# Sheet_1_2026-05-01.net
KiCad netlist of a schematic drawn in Altium Designer
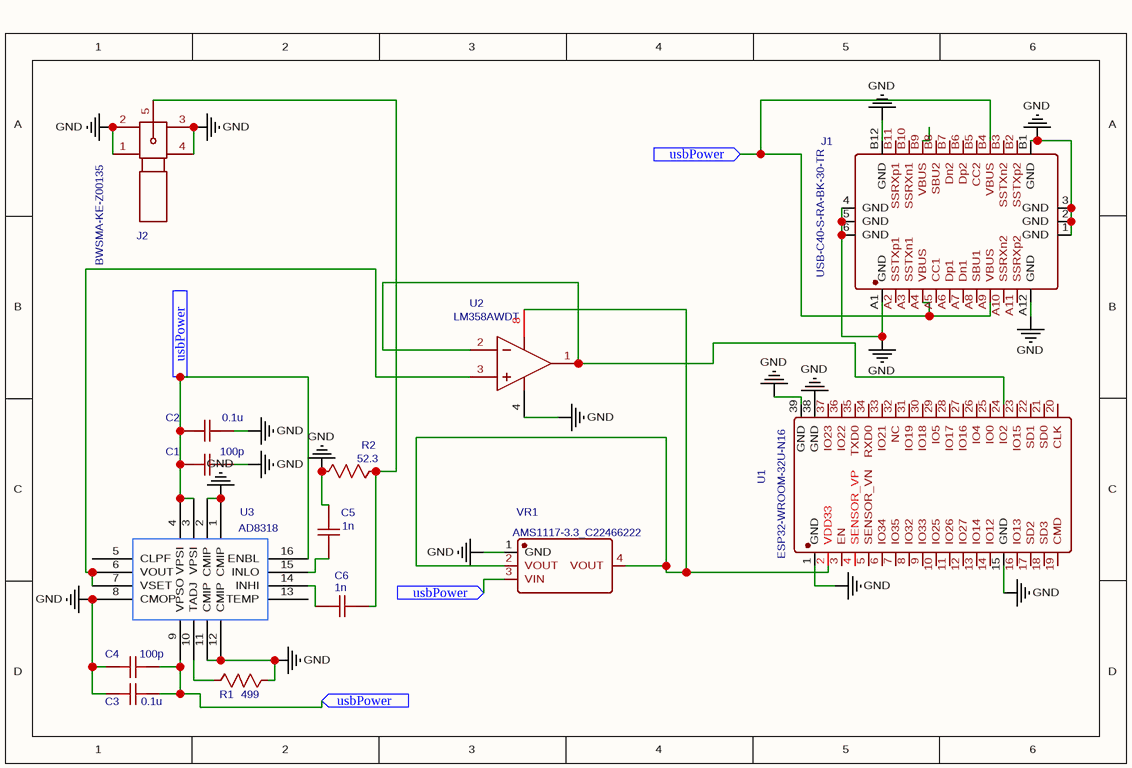
[diagram p0: Sheet_1_2026-05-01.schdoc]

(export (version "E")
  (design (tool "Eeschema 10.0.6"))
  (components
    (comp (ref "C1")
      (value "100p")
      (fields (field (name "CONTRIBUTOR") "LCEDA_Lib"))
      (libsource (lib "altium-import") (part "root_2_100p_"))
    )
    (comp (ref "C2")
      (value "0.1u")
      (fields (field (name "CONTRIBUTOR") "LCEDA_Lib"))
      (libsource (lib "altium-import") (part "root_2_0.1u_"))
    )
    (comp (ref "C3")
      (value "0.1u")
      (fields (field (name "CONTRIBUTOR") "LCEDA_Lib"))
      (libsource (lib "altium-import") (part "root_2_0.1u_"))
    )
    (comp (ref "C4")
      (value "100p")
      (fields (field (name "CONTRIBUTOR") "LCEDA_Lib"))
      (libsource (lib "altium-import") (part "root_2_100p_"))
    )
    (comp (ref "C5")
      (value "1n")
      (fields (field (name "CONTRIBUTOR") "LCEDA_Lib"))
      (libsource (lib "altium-import") (part "root_3_1n_"))
    )
    (comp (ref "C6")
      (value "1n")
      (fields (field (name "CONTRIBUTOR") "LCEDA_Lib"))
      (libsource (lib "altium-import") (part "root_2_1n_"))
    )
    (comp (ref "J1")
      (value "USB-C40-S-RA-BK-30-TR")
      (fields (field (name "MANUFACTURER") "ADAM TECH") (field (name "CONTRIBUTOR") "lcsc"))
      (libsource (lib "altium-import") (part "root_1_USB-C40-S-RA-BK-30-TR_"))
    )
    (comp (ref "J2")
      (value "BWSMA-KE-Z00135")
      (fields
        (field (name "MANUFACTURER") "LX(连欣科技)")
        (field (name "MANUFACTURER PART") "SMA-KWE/KE-135")
        (field (name "CONTRIBUTOR") "lcsc")
      )
      (libsource (lib "altium-import") (part "root_1_BWSMA-KE-Z00135_"))
    )
    (comp (ref "R1")
      (value "499")
      (fields (field (name "CONTRIBUTOR") "LCEDA_Lib"))
      (libsource (lib "altium-import") (part "root_0_499_"))
    )
    (comp (ref "R2")
      (value "52.3")
      (fields (field (name "CONTRIBUTOR") "LCEDA_Lib"))
      (libsource (lib "altium-import") (part "root_2_52.3_"))
    )
    (comp (ref "U1")
      (value "ESP32-WROOM-32U-N16")
      (fields (field (name "MANUFACTURER PART") "ESP32-WROOM-32U(16MB)") (field (name "CONTRIBUTOR") "lcsc"))
      (libsource (lib "altium-import") (part "root_1_ESP32-WROOM-32U-N16_"))
    )
    (comp (ref "U2")
      (value "LM358AWDT")
      (fields (field (name "SUBPART_NO") "1") (field (name "MANUFACTURER") "ST(意法半导体)"))
      (libsource (lib "altium-import") (part "root_0_LM358AWDT_"))
    )
    (comp (ref "U3")
      (value "AD8318")
      (fields (field (name "MANUFACTURER") "Analog Devices") (field (name "CONTRIBUTOR") "kpokigo"))
      (libsource (lib "altium-import") (part "root_3_AD8318_"))
    )
    (comp (ref "VR1")
      (value "AMS1117-3.3_C22466222")
      (fields
        (field (name "MANUFACTURER") "TDSEMIC(拓电半导体)")
        (field (name "MANUFACTURER PART") "AMS1117-3.3")
        (field (name "CONTRIBUTOR") "lcsc")
      )
      (libsource (lib "altium-import") (part "root_0_AMS1117-3.3_C22466222_"))
    )
  )
  (nets
    (net (code "1") (name "/usbPower") (class "Default")
      (node (ref "C1") (pin "2") (pinfunction "2_2") (pintype "passive"))
      (node (ref "C2") (pin "2") (pinfunction "2_2") (pintype "passive"))
      (node (ref "C3") (pin "1") (pinfunction "1_1") (pintype "passive"))
      (node (ref "C4") (pin "1") (pinfunction "1_1") (pintype "passive"))
      (node (ref "J1") (pin "A4") (pinfunction "VBUS_A4") (pintype "passive"))
      (node (ref "J1") (pin "A9") (pinfunction "VBUS_A9") (pintype "passive"))
      (node (ref "J1") (pin "B4") (pinfunction "VBUS_B4") (pintype "passive"))
      (node (ref "U3") (pin "16") (pinfunction "ENBL_16") (pintype "passive"))
      (node (ref "U3") (pin "3") (pinfunction "VPSI_3") (pintype "passive"))
      (node (ref "U3") (pin "4") (pinfunction "VPSI_4") (pintype "passive"))
      (node (ref "U3") (pin "9") (pinfunction "VPSO_9") (pintype "passive"))
      (node (ref "VR1") (pin "3") (pinfunction "VIN_3") (pintype "passive"))
    )
    (net (code "2") (name "GND") (class "Default")
      (node (ref "C1") (pin "1") (pinfunction "1_1") (pintype "passive"))
      (node (ref "C2") (pin "1") (pinfunction "1_1") (pintype "passive"))
      (node (ref "C3") (pin "2") (pinfunction "2_2") (pintype "passive"))
      (node (ref "C4") (pin "2") (pinfunction "2_2") (pintype "passive"))
      (node (ref "C5") (pin "1") (pinfunction "1_1") (pintype "passive"))
      (node (ref "J1") (pin "1") (pinfunction "GND_1") (pintype "passive"))
      (node (ref "J1") (pin "2") (pinfunction "GND_2") (pintype "passive"))
      (node (ref "J1") (pin "3") (pinfunction "GND_3") (pintype "passive"))
      (node (ref "J1") (pin "4") (pinfunction "GND_4") (pintype "passive"))
      (node (ref "J1") (pin "5") (pinfunction "GND_5") (pintype "passive"))
      (node (ref "J1") (pin "6") (pinfunction "GND_6") (pintype "passive"))
      (node (ref "J1") (pin "A1") (pinfunction "GND_A1") (pintype "passive"))
      (node (ref "J1") (pin "A12") (pinfunction "GND_A12") (pintype "passive"))
      (node (ref "J1") (pin "B1") (pinfunction "GND_B1") (pintype "passive"))
      (node (ref "J1") (pin "B12") (pinfunction "GND_B12") (pintype "passive"))
      (node (ref "J2") (pin "1") (pinfunction "1_1") (pintype "passive"))
      (node (ref "J2") (pin "2") (pinfunction "2_2") (pintype "passive"))
      (node (ref "J2") (pin "3") (pinfunction "3_3") (pintype "passive"))
      (node (ref "J2") (pin "4") (pinfunction "4_4") (pintype "passive"))
      (node (ref "R1") (pin "2") (pinfunction "2_2") (pintype "passive"))
      (node (ref "R2") (pin "2") (pinfunction "2_2") (pintype "passive"))
      (node (ref "U1") (pin "1") (pinfunction "GND_1") (pintype "passive"))
      (node (ref "U1") (pin "15") (pinfunction "GND_15") (pintype "passive"))
      (node (ref "U1") (pin "38") (pinfunction "GND_38") (pintype "passive"))
      (node (ref "U1") (pin "39") (pinfunction "GND_39") (pintype "passive"))
      (node (ref "U2") (pin "4") (pinfunction "VCC-_4") (pintype "passive"))
      (node (ref "U3") (pin "1") (pinfunction "CMIP_1") (pintype "passive"))
      (node (ref "U3") (pin "11") (pinfunction "CMIP_11") (pintype "passive"))
      (node (ref "U3") (pin "12") (pinfunction "CMIP_12") (pintype "passive"))
      (node (ref "U3") (pin "2") (pinfunction "CMIP_2") (pintype "passive"))
      (node (ref "U3") (pin "8") (pinfunction "CMOP_8") (pintype "passive"))
      (node (ref "VR1") (pin "1") (pinfunction "GND_1") (pintype "passive"))
    )
    (net (code "3") (name "Net-(C6-Pad1)") (class "Default")
      (node (ref "C6") (pin "1") (pinfunction "1_1") (pintype "passive"))
      (node (ref "J2") (pin "5") (pinfunction "5_5") (pintype "passive"))
      (node (ref "R2") (pin "1") (pinfunction "1_1") (pintype "passive"))
    )
    (net (code "4") (name "Net-(U1-IO2)") (class "Default")
      (node (ref "U1") (pin "24") (pinfunction "IO2_24") (pintype "passive"))
      (node (ref "U2") (pin "1") (pinfunction "OUT1_1") (pintype "passive"))
      (node (ref "U2") (pin "2") (pinfunction "IN1-_2") (pintype "passive"))
    )
    (net (code "5") (name "Net-(U1-VDD33)") (class "Default")
      (node (ref "U1") (pin "2") (pinfunction "VDD33_2") (pintype "passive"))
      (node (ref "U2") (pin "8") (pinfunction "VCC+_8") (pintype "passive"))
      (node (ref "VR1") (pin "2") (pinfunction "VOUT_2") (pintype "passive"))
      (node (ref "VR1") (pin "4") (pinfunction "VOUT_4") (pintype "passive"))
    )
    (net (code "6") (name "Net-(U2-IN1+)") (class "Default")
      (node (ref "U2") (pin "3") (pinfunction "IN1+_3") (pintype "passive"))
      (node (ref "U3") (pin "6") (pinfunction "VOUT_6") (pintype "passive"))
      (node (ref "U3") (pin "7") (pinfunction "VSET_7") (pintype "passive"))
    )
    (net (code "7") (name "Net-(U3-INHI)") (class "Default")
      (node (ref "C6") (pin "2") (pinfunction "2_2") (pintype "passive"))
      (node (ref "U3") (pin "14") (pinfunction "INHI_14") (pintype "passive"))
    )
    (net (code "8") (name "Net-(U3-INLO)") (class "Default")
      (node (ref "C5") (pin "2") (pinfunction "2_2") (pintype "passive"))
      (node (ref "U3") (pin "15") (pinfunction "INLO_15") (pintype "passive"))
    )
    (net (code "9") (name "Net-(U3-TADJ)") (class "Default")
      (node (ref "R1") (pin "1") (pinfunction "1_1") (pintype "passive"))
      (node (ref "U3") (pin "10") (pinfunction "TADJ_10") (pintype "passive"))
    )
    (net (code "10") (name "unconnected-(J1-CC1-PadA5)") (class "Default")
      (node (ref "J1") (pin "A5") (pinfunction "CC1_A5") (pintype "passive"))
    )
    (net (code "11") (name "unconnected-(J1-CC2-PadB5)") (class "Default")
      (node (ref "J1") (pin "B5") (pinfunction "CC2_B5") (pintype "passive"))
    )
    (net (code "12") (name "unconnected-(J1-Dn1-PadA7)") (class "Default")
      (node (ref "J1") (pin "A7") (pinfunction "Dn1_A7") (pintype "passive"))
    )
    (net (code "13") (name "unconnected-(J1-Dn2-PadB7)") (class "Default")
      (node (ref "J1") (pin "B7") (pinfunction "Dn2_B7") (pintype "passive"))
    )
    (net (code "14") (name "unconnected-(J1-Dp1-PadA6)") (class "Default")
      (node (ref "J1") (pin "A6") (pinfunction "Dp1_A6") (pintype "passive"))
    )
    (net (code "15") (name "unconnected-(J1-Dp2-PadB6)") (class "Default")
      (node (ref "J1") (pin "B6") (pinfunction "Dp2_B6") (pintype "passive"))
    )
    (net (code "16") (name "unconnected-(J1-SBU1-PadA8)") (class "Default")
      (node (ref "J1") (pin "A8") (pinfunction "SBU1_A8") (pintype "passive"))
    )
    (net (code "17") (name "unconnected-(J1-SBU2-PadB8)") (class "Default")
      (node (ref "J1") (pin "B8") (pinfunction "SBU2_B8") (pintype "passive"))
    )
    (net (code "18") (name "unconnected-(J1-SSRXn1-PadB10)") (class "Default")
      (node (ref "J1") (pin "B10") (pinfunction "SSRXn1_B10") (pintype "passive"))
    )
    (net (code "19") (name "unconnected-(J1-SSRXn2-PadA10)") (class "Default")
      (node (ref "J1") (pin "A10") (pinfunction "SSRXn2_A10") (pintype "passive"))
    )
    (net (code "20") (name "unconnected-(J1-SSRXp1-PadB11)") (class "Default")
      (node (ref "J1") (pin "B11") (pinfunction "SSRXp1_B11") (pintype "passive"))
    )
    (net (code "21") (name "unconnected-(J1-SSRXp2-PadA11)") (class "Default")
      (node (ref "J1") (pin "A11") (pinfunction "SSRXp2_A11") (pintype "passive"))
    )
    (net (code "22") (name "unconnected-(J1-SSTXn1-PadA3)") (class "Default")
      (node (ref "J1") (pin "A3") (pinfunction "SSTXn1_A3") (pintype "passive"))
    )
    (net (code "23") (name "unconnected-(J1-SSTXn2-PadB3)") (class "Default")
      (node (ref "J1") (pin "B3") (pinfunction "SSTXn2_B3") (pintype "passive"))
    )
    (net (code "24") (name "unconnected-(J1-SSTXp1-PadA2)") (class "Default")
      (node (ref "J1") (pin "A2") (pinfunction "SSTXp1_A2") (pintype "passive"))
    )
    (net (code "25") (name "unconnected-(J1-SSTXp2-PadB2)") (class "Default")
      (node (ref "J1") (pin "B2") (pinfunction "SSTXp2_B2") (pintype "passive"))
    )
    (net (code "26") (name "unconnected-(J1-VBUS-PadB9)") (class "Default")
      (node (ref "J1") (pin "B9") (pinfunction "VBUS_B9") (pintype "passive"))
    )
    (net (code "27") (name "unconnected-(U1-CLK-Pad20)") (class "Default")
      (node (ref "U1") (pin "20") (pinfunction "CLK_20") (pintype "passive"))
    )
    (net (code "28") (name "unconnected-(U1-CMD-Pad19)") (class "Default")
      (node (ref "U1") (pin "19") (pinfunction "CMD_19") (pintype "passive"))
    )
    (net (code "29") (name "unconnected-(U1-EN-Pad3)") (class "Default")
      (node (ref "U1") (pin "3") (pinfunction "EN_3") (pintype "passive"))
    )
    (net (code "30") (name "unconnected-(U1-IO0-Pad25)") (class "Default")
      (node (ref "U1") (pin "25") (pinfunction "IO0_25") (pintype "passive"))
    )
    (net (code "31") (name "unconnected-(U1-IO4-Pad26)") (class "Default")
      (node (ref "U1") (pin "26") (pinfunction "IO4_26") (pintype "passive"))
    )
    (net (code "32") (name "unconnected-(U1-IO5-Pad29)") (class "Default")
      (node (ref "U1") (pin "29") (pinfunction "IO5_29") (pintype "passive"))
    )
    (net (code "33") (name "unconnected-(U1-IO12-Pad14)") (class "Default")
      (node (ref "U1") (pin "14") (pinfunction "IO12_14") (pintype "passive"))
    )
    (net (code "34") (name "unconnected-(U1-IO13-Pad16)") (class "Default")
      (node (ref "U1") (pin "16") (pinfunction "IO13_16") (pintype "passive"))
    )
    (net (code "35") (name "unconnected-(U1-IO14-Pad13)") (class "Default")
      (node (ref "U1") (pin "13") (pinfunction "IO14_13") (pintype "passive"))
    )
    (net (code "36") (name "unconnected-(U1-IO15-Pad23)") (class "Default")
      (node (ref "U1") (pin "23") (pinfunction "IO15_23") (pintype "passive"))
    )
    (net (code "37") (name "unconnected-(U1-IO16-Pad27)") (class "Default")
      (node (ref "U1") (pin "27") (pinfunction "IO16_27") (pintype "passive"))
    )
    (net (code "38") (name "unconnected-(U1-IO17-Pad28)") (class "Default")
      (node (ref "U1") (pin "28") (pinfunction "IO17_28") (pintype "passive"))
    )
    (net (code "39") (name "unconnected-(U1-IO18-Pad30)") (class "Default")
      (node (ref "U1") (pin "30") (pinfunction "IO18_30") (pintype "passive"))
    )
    (net (code "40") (name "unconnected-(U1-IO19-Pad31)") (class "Default")
      (node (ref "U1") (pin "31") (pinfunction "IO19_31") (pintype "passive"))
    )
    (net (code "41") (name "unconnected-(U1-IO21-Pad33)") (class "Default")
      (node (ref "U1") (pin "33") (pinfunction "IO21_33") (pintype "passive"))
    )
    (net (code "42") (name "unconnected-(U1-IO22-Pad36)") (class "Default")
      (node (ref "U1") (pin "36") (pinfunction "IO22_36") (pintype "passive"))
    )
    (net (code "43") (name "unconnected-(U1-IO23-Pad37)") (class "Default")
      (node (ref "U1") (pin "37") (pinfunction "IO23_37") (pintype "passive"))
    )
    (net (code "44") (name "unconnected-(U1-IO25-Pad10)") (class "Default")
      (node (ref "U1") (pin "10") (pinfunction "IO25_10") (pintype "passive"))
    )
    (net (code "45") (name "unconnected-(U1-IO26-Pad11)") (class "Default")
      (node (ref "U1") (pin "11") (pinfunction "IO26_11") (pintype "passive"))
    )
    (net (code "46") (name "unconnected-(U1-IO27-Pad12)") (class "Default")
      (node (ref "U1") (pin "12") (pinfunction "IO27_12") (pintype "passive"))
    )
    (net (code "47") (name "unconnected-(U1-IO32-Pad8)") (class "Default")
      (node (ref "U1") (pin "8") (pinfunction "IO32_8") (pintype "passive"))
    )
    (net (code "48") (name "unconnected-(U1-IO33-Pad9)") (class "Default")
      (node (ref "U1") (pin "9") (pinfunction "IO33_9") (pintype "passive"))
    )
    (net (code "49") (name "unconnected-(U1-IO34-Pad6)") (class "Default")
      (node (ref "U1") (pin "6") (pinfunction "IO34_6") (pintype "passive"))
    )
    (net (code "50") (name "unconnected-(U1-IO35-Pad7)") (class "Default")
      (node (ref "U1") (pin "7") (pinfunction "IO35_7") (pintype "passive"))
    )
    (net (code "51") (name "unconnected-(U1-NC-Pad32)") (class "Default")
      (node (ref "U1") (pin "32") (pinfunction "NC_32") (pintype "passive"))
    )
    (net (code "52") (name "unconnected-(U1-RXD0-Pad34)") (class "Default")
      (node (ref "U1") (pin "34") (pinfunction "RXD0_34") (pintype "passive"))
    )
    (net (code "53") (name "unconnected-(U1-SD0-Pad21)") (class "Default")
      (node (ref "U1") (pin "21") (pinfunction "SD0_21") (pintype "passive"))
    )
    (net (code "54") (name "unconnected-(U1-SD1-Pad22)") (class "Default")
      (node (ref "U1") (pin "22") (pinfunction "SD1_22") (pintype "passive"))
    )
    (net (code "55") (name "unconnected-(U1-SD2-Pad17)") (class "Default")
      (node (ref "U1") (pin "17") (pinfunction "SD2_17") (pintype "passive"))
    )
    (net (code "56") (name "unconnected-(U1-SD3-Pad18)") (class "Default")
      (node (ref "U1") (pin "18") (pinfunction "SD3_18") (pintype "passive"))
    )
    (net (code "57") (name "unconnected-(U1-SENSOR_VN-Pad5)") (class "Default")
      (node (ref "U1") (pin "5") (pinfunction "SENSOR_VN_5") (pintype "passive"))
    )
    (net (code "58") (name "unconnected-(U1-SENSOR_VP-Pad4)") (class "Default")
      (node (ref "U1") (pin "4") (pinfunction "SENSOR_VP_4") (pintype "passive"))
    )
    (net (code "59") (name "unconnected-(U1-TXD0-Pad35)") (class "Default")
      (node (ref "U1") (pin "35") (pinfunction "TXD0_35") (pintype "passive"))
    )
    (net (code "60") (name "unconnected-(U3-CLPF-Pad5)") (class "Default")
      (node (ref "U3") (pin "5") (pinfunction "CLPF_5") (pintype "passive"))
    )
    (net (code "61") (name "unconnected-(U3-TEMP-Pad13)") (class "Default")
      (node (ref "U3") (pin "13") (pinfunction "TEMP_13") (pintype "passive"))
    )
  )
)
